# pcb.net
KiCad netlist of a schematic drawn in EasyEDA Pro
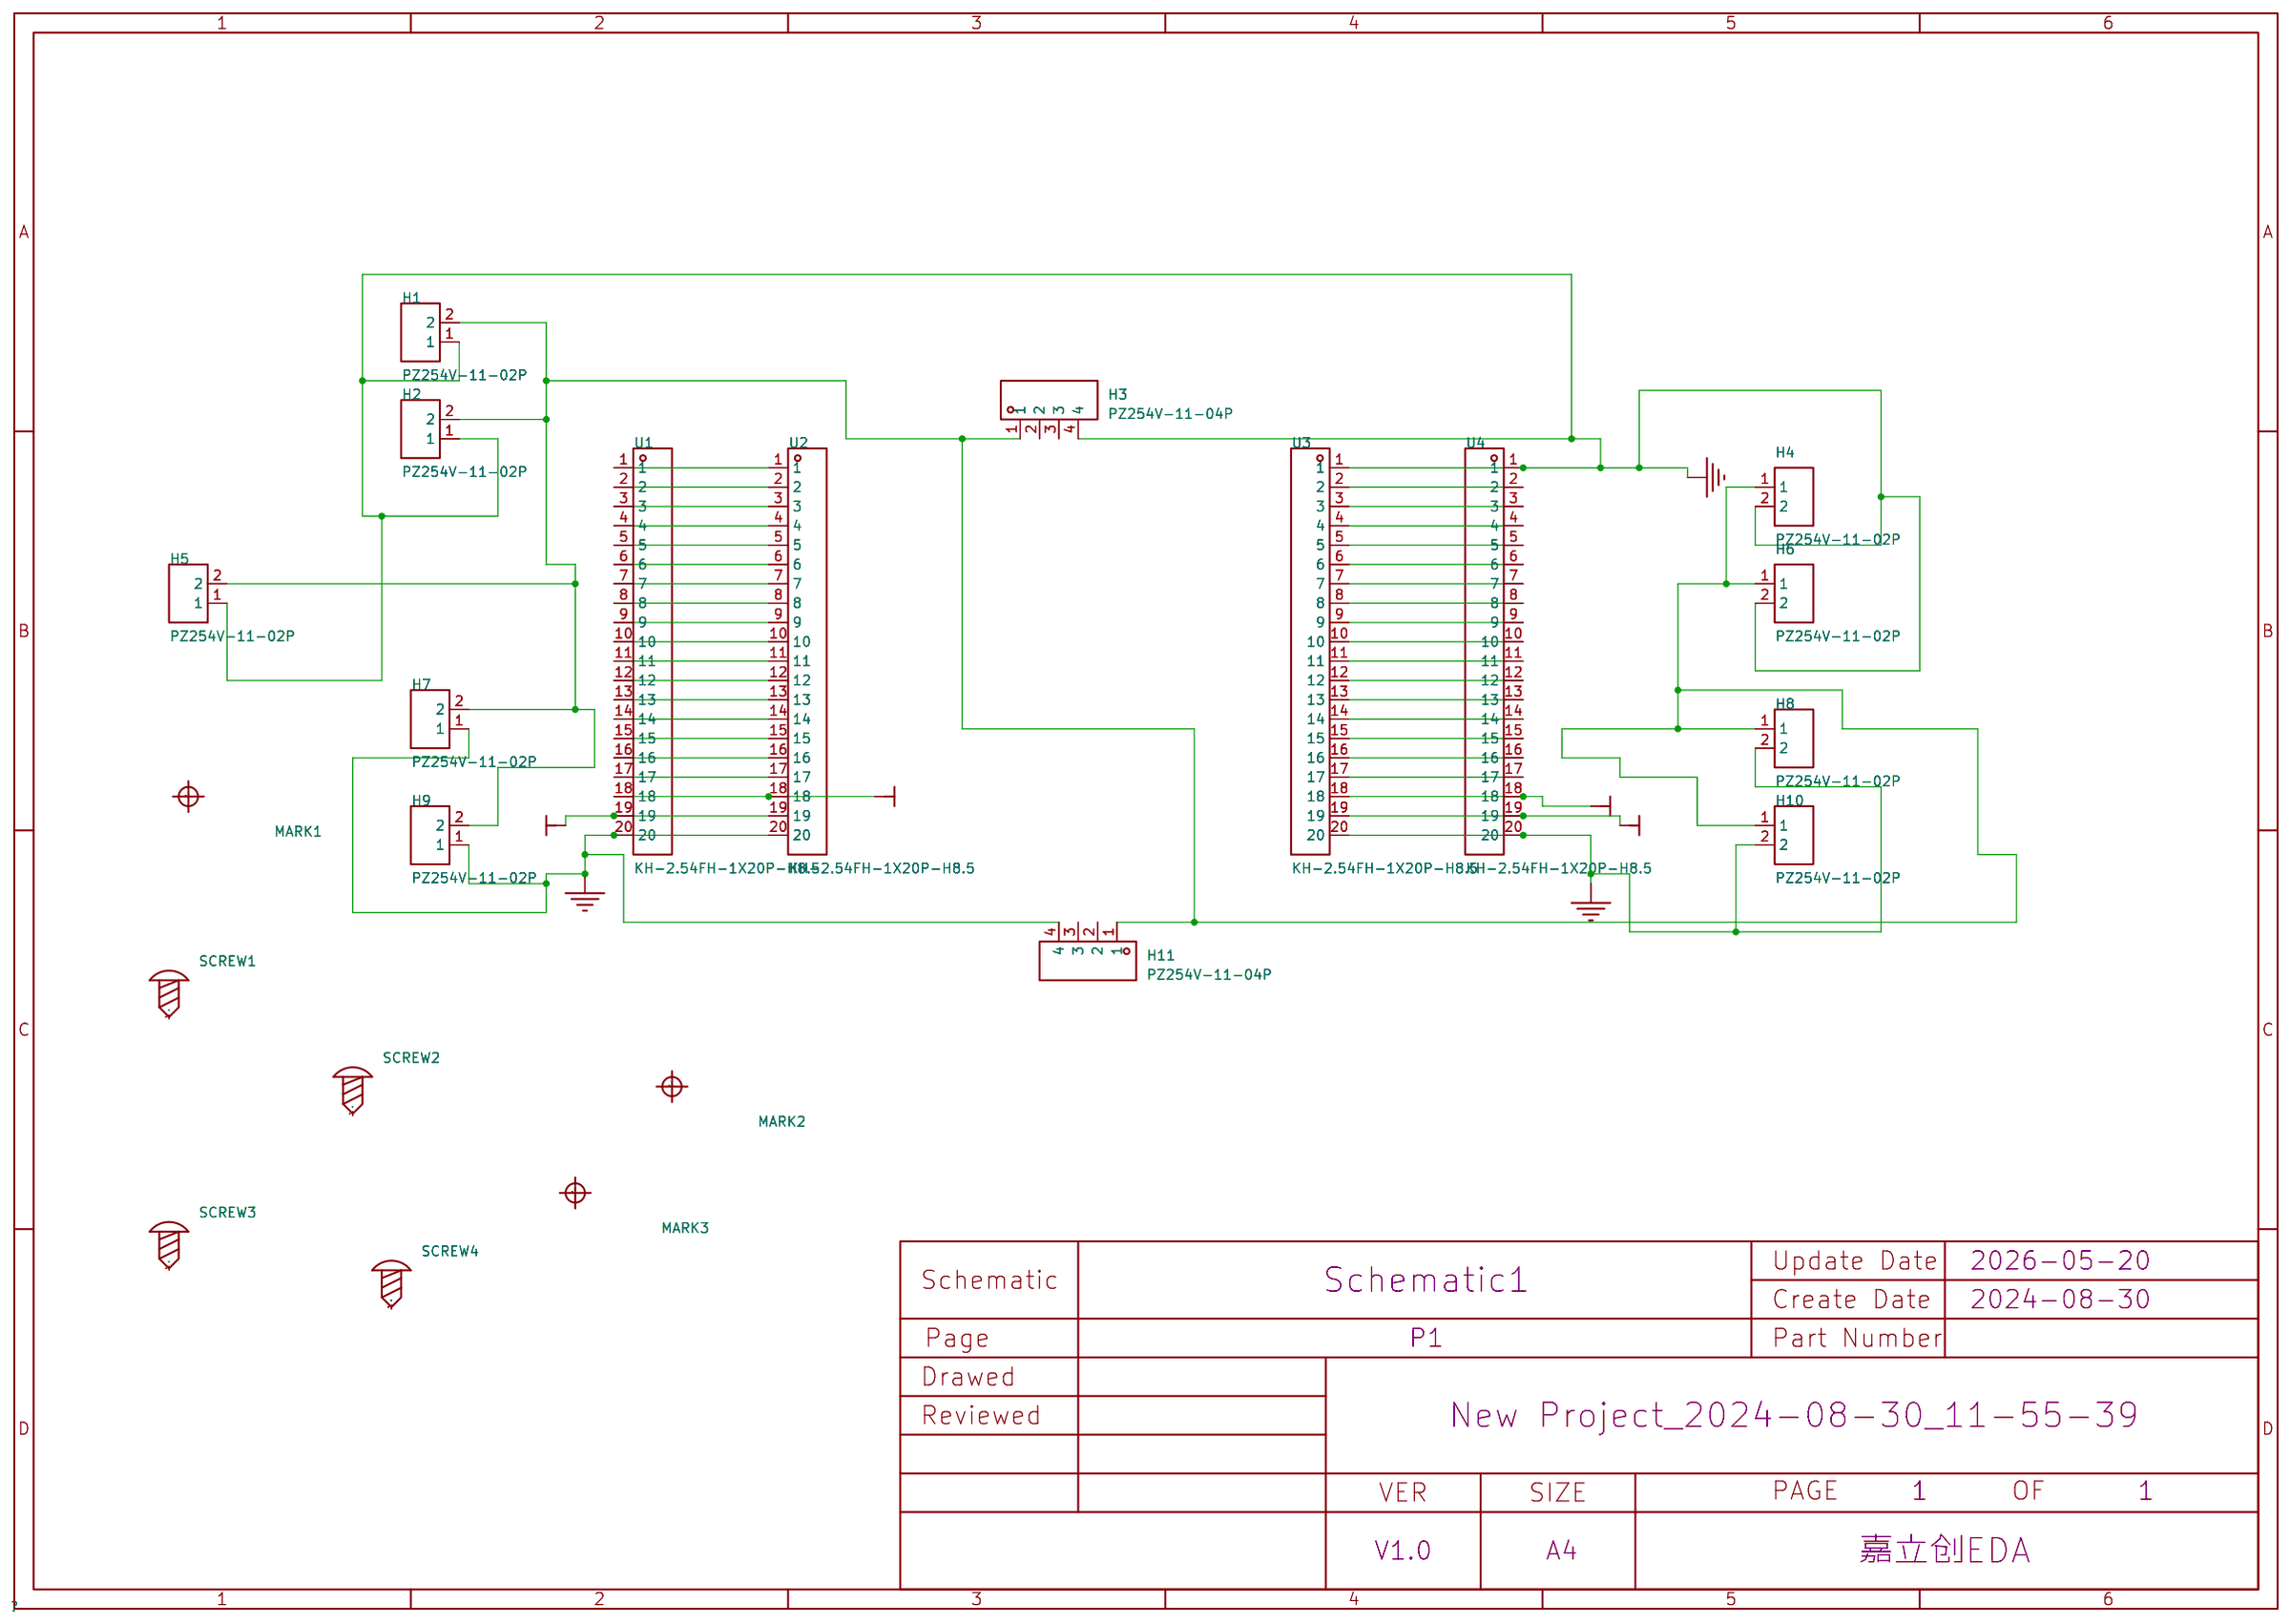
[diagram p0: schematic sheet]

(export (version "E")
  (design (tool "Eeschema 10.0.6"))
  (components
    (comp (ref "H1")
      (value "PZ254V-11-02P")
      (footprint "easyedapro:HDR-TH_2P-P2.54-V-M")
      (fields (field (name "Manufacturer") "XFCN(兴飞)"))
      (libsource (lib "easyedapro") (part "PZ254V-11-02P"))
    )
    (comp (ref "H2")
      (value "PZ254V-11-02P")
      (footprint "easyedapro:HDR-TH_2P-P2.54-V-M")
      (fields (field (name "Manufacturer") "XFCN(兴飞)"))
      (libsource (lib "easyedapro") (part "PZ254V-11-02P"))
    )
    (comp (ref "H3")
      (value "PZ254V-11-04P")
      (footprint "easyedapro:HDR-TH_4P-P2.54-V-M")
      (fields (field (name "Manufacturer") "XFCN(兴飞)"))
      (libsource (lib "easyedapro") (part "PZ254V-11-04P_C2691448"))
    )
    (comp (ref "H4")
      (value "PZ254V-11-02P")
      (footprint "easyedapro:HDR-TH_2P-P2.54-V-M")
      (fields (field (name "Manufacturer") "XFCN(兴飞)"))
      (libsource (lib "easyedapro") (part "PZ254V-11-02P"))
    )
    (comp (ref "H5")
      (value "PZ254V-11-02P")
      (footprint "easyedapro:HDR-TH_2P-P2.54-V-M")
      (fields (field (name "Manufacturer") "XFCN(兴飞)"))
      (libsource (lib "easyedapro") (part "PZ254V-11-02P"))
    )
    (comp (ref "H6")
      (value "PZ254V-11-02P")
      (footprint "easyedapro:HDR-TH_2P-P2.54-V-M")
      (fields (field (name "Manufacturer") "XFCN(兴飞)"))
      (libsource (lib "easyedapro") (part "PZ254V-11-02P"))
    )
    (comp (ref "H7")
      (value "PZ254V-11-02P")
      (footprint "easyedapro:HDR-TH_2P-P2.54-V-M")
      (fields (field (name "Manufacturer") "XFCN(兴飞)"))
      (libsource (lib "easyedapro") (part "PZ254V-11-02P"))
    )
    (comp (ref "H8")
      (value "PZ254V-11-02P")
      (footprint "easyedapro:HDR-TH_2P-P2.54-V-M")
      (fields (field (name "Manufacturer") "XFCN(兴飞)"))
      (libsource (lib "easyedapro") (part "PZ254V-11-02P"))
    )
    (comp (ref "H9")
      (value "PZ254V-11-02P")
      (footprint "easyedapro:HDR-TH_2P-P2.54-V-M")
      (fields (field (name "Manufacturer") "XFCN(兴飞)"))
      (libsource (lib "easyedapro") (part "PZ254V-11-02P"))
    )
    (comp (ref "H10")
      (value "PZ254V-11-02P")
      (footprint "easyedapro:HDR-TH_2P-P2.54-V-M")
      (fields (field (name "Manufacturer") "XFCN(兴飞)"))
      (libsource (lib "easyedapro") (part "PZ254V-11-02P"))
    )
    (comp (ref "H11")
      (value "PZ254V-11-04P")
      (footprint "easyedapro:HDR-TH_4P-P2.54-V-M")
      (fields (field (name "Manufacturer") "XFCN(兴飞)"))
      (libsource (lib "easyedapro") (part "PZ254V-11-04P_C2691448"))
    )
    (comp (ref "MARK1")
      (value "~")
      (footprint "easyedapro:Mark-Point-1mm")
      (libsource (lib "easyedapro") (part "Mark-Point"))
    )
    (comp (ref "MARK2")
      (value "~")
      (footprint "easyedapro:Mark-Point-1mm")
      (libsource (lib "easyedapro") (part "Mark-Point"))
    )
    (comp (ref "MARK3")
      (value "~")
      (footprint "easyedapro:Mark-Point-1mm")
      (libsource (lib "easyedapro") (part "Mark-Point"))
    )
    (comp (ref "SCREW1")
      (value "~")
      (footprint "easyedapro:M3螺丝")
      (libsource (lib "easyedapro") (part "螺丝孔"))
    )
    (comp (ref "SCREW2")
      (value "~")
      (footprint "easyedapro:M3螺丝")
      (libsource (lib "easyedapro") (part "螺丝孔"))
    )
    (comp (ref "SCREW3")
      (value "~")
      (footprint "easyedapro:M3螺丝")
      (libsource (lib "easyedapro") (part "螺丝孔"))
    )
    (comp (ref "SCREW4")
      (value "~")
      (footprint "easyedapro:M3螺丝")
      (libsource (lib "easyedapro") (part "螺丝孔"))
    )
    (comp (ref "U1")
      (value "KH-2.54FH-1X20P-H8.5")
      (footprint "easyedapro:HDR-TH_20P-P2.54-V-F-2")
      (fields (field (name "Manufacturer") "kinghelm(金航标)"))
      (libsource (lib "easyedapro") (part "KH-2.54FH-1X20P-H8.5"))
    )
    (comp (ref "U2")
      (value "KH-2.54FH-1X20P-H8.5")
      (footprint "easyedapro:HDR-TH_20P-P2.54-V-F-2")
      (fields (field (name "Manufacturer") "kinghelm(金航标)"))
      (libsource (lib "easyedapro") (part "KH-2.54FH-1X20P-H8.5"))
    )
    (comp (ref "U3")
      (value "KH-2.54FH-1X20P-H8.5")
      (footprint "easyedapro:HDR-TH_20P-P2.54-V-F-2")
      (fields (field (name "Manufacturer") "kinghelm(金航标)"))
      (libsource (lib "easyedapro") (part "KH-2.54FH-1X20P-H8.5"))
    )
    (comp (ref "U4")
      (value "KH-2.54FH-1X20P-H8.5")
      (footprint "easyedapro:HDR-TH_20P-P2.54-V-F-2")
      (fields (field (name "Manufacturer") "kinghelm(金航标)"))
      (libsource (lib "easyedapro") (part "KH-2.54FH-1X20P-H8.5"))
    )
  )
  (nets
    (net (code "1") (name "3.3V") (class "Default")
      (node (ref "U1") (pin "19") (pinfunction "19_19") (pintype "unspecified"))
      (node (ref "U2") (pin "19") (pinfunction "19_19") (pintype "unspecified"))
      (node (ref "U3") (pin "19") (pinfunction "19_19") (pintype "unspecified"))
      (node (ref "U4") (pin "19") (pinfunction "19_19") (pintype "unspecified"))
    )
    (net (code "2") (name "5V") (class "Default")
      (node (ref "U1") (pin "18") (pinfunction "18_18") (pintype "unspecified"))
      (node (ref "U2") (pin "18") (pinfunction "18_18") (pintype "unspecified"))
      (node (ref "U3") (pin "18") (pinfunction "18_18") (pintype "unspecified"))
      (node (ref "U4") (pin "18") (pinfunction "18_18") (pintype "unspecified"))
    )
    (net (code "3") (name "GND") (class "Default")
      (node (ref "H1") (pin "1") (pinfunction "1_1") (pintype "unspecified"))
      (node (ref "H10") (pin "2") (pinfunction "2_2") (pintype "unspecified"))
      (node (ref "H11") (pin "4") (pinfunction "4_4") (pintype "unspecified"))
      (node (ref "H2") (pin "1") (pinfunction "1_1") (pintype "unspecified"))
      (node (ref "H3") (pin "4") (pinfunction "4_4") (pintype "unspecified"))
      (node (ref "H4") (pin "2") (pinfunction "2_2") (pintype "unspecified"))
      (node (ref "H5") (pin "1") (pinfunction "1_1") (pintype "unspecified"))
      (node (ref "H6") (pin "2") (pinfunction "2_2") (pintype "unspecified"))
      (node (ref "H7") (pin "1") (pinfunction "1_1") (pintype "unspecified"))
      (node (ref "H8") (pin "2") (pinfunction "2_2") (pintype "unspecified"))
      (node (ref "H9") (pin "1") (pinfunction "1_1") (pintype "unspecified"))
      (node (ref "U1") (pin "20") (pinfunction "20_20") (pintype "unspecified"))
      (node (ref "U2") (pin "20") (pinfunction "20_20") (pintype "unspecified"))
      (node (ref "U3") (pin "1") (pinfunction "1_1") (pintype "unspecified"))
      (node (ref "U3") (pin "20") (pinfunction "20_20") (pintype "unspecified"))
      (node (ref "U4") (pin "1") (pinfunction "1_1") (pintype "unspecified"))
      (node (ref "U4") (pin "20") (pinfunction "20_20") (pintype "unspecified"))
    )
    (net (code "4") (name "Net-(H1-Pad2)") (class "Default")
      (node (ref "H1") (pin "2") (pinfunction "2_2") (pintype "unspecified"))
      (node (ref "H10") (pin "1") (pinfunction "1_1") (pintype "unspecified"))
      (node (ref "H11") (pin "1") (pinfunction "1_1") (pintype "unspecified"))
      (node (ref "H2") (pin "2") (pinfunction "2_2") (pintype "unspecified"))
      (node (ref "H3") (pin "1") (pinfunction "1_1") (pintype "unspecified"))
      (node (ref "H4") (pin "1") (pinfunction "1_1") (pintype "unspecified"))
      (node (ref "H5") (pin "2") (pinfunction "2_2") (pintype "unspecified"))
      (node (ref "H6") (pin "1") (pinfunction "1_1") (pintype "unspecified"))
      (node (ref "H7") (pin "2") (pinfunction "2_2") (pintype "unspecified"))
      (node (ref "H8") (pin "1") (pinfunction "1_1") (pintype "unspecified"))
      (node (ref "H9") (pin "2") (pinfunction "2_2") (pintype "unspecified"))
    )
    (net (code "5") (name "Net-(U1-Pad1)") (class "Default")
      (node (ref "U1") (pin "1") (pinfunction "1_1") (pintype "unspecified"))
      (node (ref "U2") (pin "1") (pinfunction "1_1") (pintype "unspecified"))
    )
    (net (code "6") (name "Net-(U1-Pad2)") (class "Default")
      (node (ref "U1") (pin "2") (pinfunction "2_2") (pintype "unspecified"))
      (node (ref "U2") (pin "2") (pinfunction "2_2") (pintype "unspecified"))
    )
    (net (code "7") (name "Net-(U1-Pad3)") (class "Default")
      (node (ref "U1") (pin "3") (pinfunction "3_3") (pintype "unspecified"))
      (node (ref "U2") (pin "3") (pinfunction "3_3") (pintype "unspecified"))
    )
    (net (code "8") (name "Net-(U1-Pad4)") (class "Default")
      (node (ref "U1") (pin "4") (pinfunction "4_4") (pintype "unspecified"))
      (node (ref "U2") (pin "4") (pinfunction "4_4") (pintype "unspecified"))
    )
    (net (code "9") (name "Net-(U1-Pad5)") (class "Default")
      (node (ref "U1") (pin "5") (pinfunction "5_5") (pintype "unspecified"))
      (node (ref "U2") (pin "5") (pinfunction "5_5") (pintype "unspecified"))
    )
    (net (code "10") (name "Net-(U1-Pad6)") (class "Default")
      (node (ref "U1") (pin "6") (pinfunction "6_6") (pintype "unspecified"))
      (node (ref "U2") (pin "6") (pinfunction "6_6") (pintype "unspecified"))
    )
    (net (code "11") (name "Net-(U1-Pad7)") (class "Default")
      (node (ref "U1") (pin "7") (pinfunction "7_7") (pintype "unspecified"))
      (node (ref "U2") (pin "7") (pinfunction "7_7") (pintype "unspecified"))
    )
    (net (code "12") (name "Net-(U1-Pad8)") (class "Default")
      (node (ref "U1") (pin "8") (pinfunction "8_8") (pintype "unspecified"))
      (node (ref "U2") (pin "8") (pinfunction "8_8") (pintype "unspecified"))
    )
    (net (code "13") (name "Net-(U1-Pad9)") (class "Default")
      (node (ref "U1") (pin "9") (pinfunction "9_9") (pintype "unspecified"))
      (node (ref "U2") (pin "9") (pinfunction "9_9") (pintype "unspecified"))
    )
    (net (code "14") (name "Net-(U1-Pad10)") (class "Default")
      (node (ref "U1") (pin "10") (pinfunction "10_10") (pintype "unspecified"))
      (node (ref "U2") (pin "10") (pinfunction "10_10") (pintype "unspecified"))
    )
    (net (code "15") (name "Net-(U1-Pad11)") (class "Default")
      (node (ref "U1") (pin "11") (pinfunction "11_11") (pintype "unspecified"))
      (node (ref "U2") (pin "11") (pinfunction "11_11") (pintype "unspecified"))
    )
    (net (code "16") (name "Net-(U1-Pad12)") (class "Default")
      (node (ref "U1") (pin "12") (pinfunction "12_12") (pintype "unspecified"))
      (node (ref "U2") (pin "12") (pinfunction "12_12") (pintype "unspecified"))
    )
    (net (code "17") (name "Net-(U1-Pad13)") (class "Default")
      (node (ref "U1") (pin "13") (pinfunction "13_13") (pintype "unspecified"))
      (node (ref "U2") (pin "13") (pinfunction "13_13") (pintype "unspecified"))
    )
    (net (code "18") (name "Net-(U1-Pad14)") (class "Default")
      (node (ref "U1") (pin "14") (pinfunction "14_14") (pintype "unspecified"))
      (node (ref "U2") (pin "14") (pinfunction "14_14") (pintype "unspecified"))
    )
    (net (code "19") (name "Net-(U1-Pad15)") (class "Default")
      (node (ref "U1") (pin "15") (pinfunction "15_15") (pintype "unspecified"))
      (node (ref "U2") (pin "15") (pinfunction "15_15") (pintype "unspecified"))
    )
    (net (code "20") (name "Net-(U1-Pad16)") (class "Default")
      (node (ref "U1") (pin "16") (pinfunction "16_16") (pintype "unspecified"))
      (node (ref "U2") (pin "16") (pinfunction "16_16") (pintype "unspecified"))
    )
    (net (code "21") (name "Net-(U1-Pad17)") (class "Default")
      (node (ref "U1") (pin "17") (pinfunction "17_17") (pintype "unspecified"))
      (node (ref "U2") (pin "17") (pinfunction "17_17") (pintype "unspecified"))
    )
    (net (code "22") (name "Net-(U3-Pad2)") (class "Default")
      (node (ref "U3") (pin "2") (pinfunction "2_2") (pintype "unspecified"))
      (node (ref "U4") (pin "2") (pinfunction "2_2") (pintype "unspecified"))
    )
    (net (code "23") (name "Net-(U3-Pad3)") (class "Default")
      (node (ref "U3") (pin "3") (pinfunction "3_3") (pintype "unspecified"))
      (node (ref "U4") (pin "3") (pinfunction "3_3") (pintype "unspecified"))
    )
    (net (code "24") (name "Net-(U3-Pad4)") (class "Default")
      (node (ref "U3") (pin "4") (pinfunction "4_4") (pintype "unspecified"))
      (node (ref "U4") (pin "4") (pinfunction "4_4") (pintype "unspecified"))
    )
    (net (code "25") (name "Net-(U3-Pad5)") (class "Default")
      (node (ref "U3") (pin "5") (pinfunction "5_5") (pintype "unspecified"))
      (node (ref "U4") (pin "5") (pinfunction "5_5") (pintype "unspecified"))
    )
    (net (code "26") (name "Net-(U3-Pad6)") (class "Default")
      (node (ref "U3") (pin "6") (pinfunction "6_6") (pintype "unspecified"))
      (node (ref "U4") (pin "6") (pinfunction "6_6") (pintype "unspecified"))
    )
    (net (code "27") (name "Net-(U3-Pad7)") (class "Default")
      (node (ref "U3") (pin "7") (pinfunction "7_7") (pintype "unspecified"))
      (node (ref "U4") (pin "7") (pinfunction "7_7") (pintype "unspecified"))
    )
    (net (code "28") (name "Net-(U3-Pad8)") (class "Default")
      (node (ref "U3") (pin "8") (pinfunction "8_8") (pintype "unspecified"))
      (node (ref "U4") (pin "8") (pinfunction "8_8") (pintype "unspecified"))
    )
    (net (code "29") (name "Net-(U3-Pad9)") (class "Default")
      (node (ref "U3") (pin "9") (pinfunction "9_9") (pintype "unspecified"))
      (node (ref "U4") (pin "9") (pinfunction "9_9") (pintype "unspecified"))
    )
    (net (code "30") (name "Net-(U3-Pad10)") (class "Default")
      (node (ref "U3") (pin "10") (pinfunction "10_10") (pintype "unspecified"))
      (node (ref "U4") (pin "10") (pinfunction "10_10") (pintype "unspecified"))
    )
    (net (code "31") (name "Net-(U3-Pad11)") (class "Default")
      (node (ref "U3") (pin "11") (pinfunction "11_11") (pintype "unspecified"))
      (node (ref "U4") (pin "11") (pinfunction "11_11") (pintype "unspecified"))
    )
    (net (code "32") (name "Net-(U3-Pad12)") (class "Default")
      (node (ref "U3") (pin "12") (pinfunction "12_12") (pintype "unspecified"))
      (node (ref "U4") (pin "12") (pinfunction "12_12") (pintype "unspecified"))
    )
    (net (code "33") (name "Net-(U3-Pad13)") (class "Default")
      (node (ref "U3") (pin "13") (pinfunction "13_13") (pintype "unspecified"))
      (node (ref "U4") (pin "13") (pinfunction "13_13") (pintype "unspecified"))
    )
    (net (code "34") (name "Net-(U3-Pad14)") (class "Default")
      (node (ref "U3") (pin "14") (pinfunction "14_14") (pintype "unspecified"))
      (node (ref "U4") (pin "14") (pinfunction "14_14") (pintype "unspecified"))
    )
    (net (code "35") (name "Net-(U3-Pad15)") (class "Default")
      (node (ref "U3") (pin "15") (pinfunction "15_15") (pintype "unspecified"))
      (node (ref "U4") (pin "15") (pinfunction "15_15") (pintype "unspecified"))
    )
    (net (code "36") (name "Net-(U3-Pad16)") (class "Default")
      (node (ref "U3") (pin "16") (pinfunction "16_16") (pintype "unspecified"))
      (node (ref "U4") (pin "16") (pinfunction "16_16") (pintype "unspecified"))
    )
    (net (code "37") (name "Net-(U3-Pad17)") (class "Default")
      (node (ref "U3") (pin "17") (pinfunction "17_17") (pintype "unspecified"))
      (node (ref "U4") (pin "17") (pinfunction "17_17") (pintype "unspecified"))
    )
    (net (code "38") (name "unconnected-(H3-Pad2)") (class "Default")
      (node (ref "H3") (pin "2") (pinfunction "2_2") (pintype "unspecified"))
    )
    (net (code "39") (name "unconnected-(H3-Pad3)") (class "Default")
      (node (ref "H3") (pin "3") (pinfunction "3_3") (pintype "unspecified"))
    )
    (net (code "40") (name "unconnected-(H11-Pad2)") (class "Default")
      (node (ref "H11") (pin "2") (pinfunction "2_2") (pintype "unspecified"))
    )
    (net (code "41") (name "unconnected-(H11-Pad3)") (class "Default")
      (node (ref "H11") (pin "3") (pinfunction "3_3") (pintype "unspecified"))
    )
    (net (code "42") (name "unconnected-(MARK1-Pad1)") (class "Default")
      (node (ref "MARK1") (pin "1") (pinfunction "1_1") (pintype "input"))
    )
    (net (code "43") (name "unconnected-(MARK2-Pad1)") (class "Default")
      (node (ref "MARK2") (pin "1") (pinfunction "1_1") (pintype "input"))
    )
    (net (code "44") (name "unconnected-(MARK3-Pad1)") (class "Default")
      (node (ref "MARK3") (pin "1") (pinfunction "1_1") (pintype "input"))
    )
    (net (code "45") (name "unconnected-(SCREW1-Pad1)") (class "Default")
      (node (ref "SCREW1") (pin "1") (pinfunction "1_1") (pintype "input"))
    )
    (net (code "46") (name "unconnected-(SCREW2-Pad1)") (class "Default")
      (node (ref "SCREW2") (pin "1") (pinfunction "1_1") (pintype "input"))
    )
    (net (code "47") (name "unconnected-(SCREW3-Pad1)") (class "Default")
      (node (ref "SCREW3") (pin "1") (pinfunction "1_1") (pintype "input"))
    )
    (net (code "48") (name "unconnected-(SCREW4-Pad1)") (class "Default")
      (node (ref "SCREW4") (pin "1") (pinfunction "1_1") (pintype "input"))
    )
  )
)
